# CircuitTestZak1.net
KiCad netlist of a schematic drawn in Altium Designer
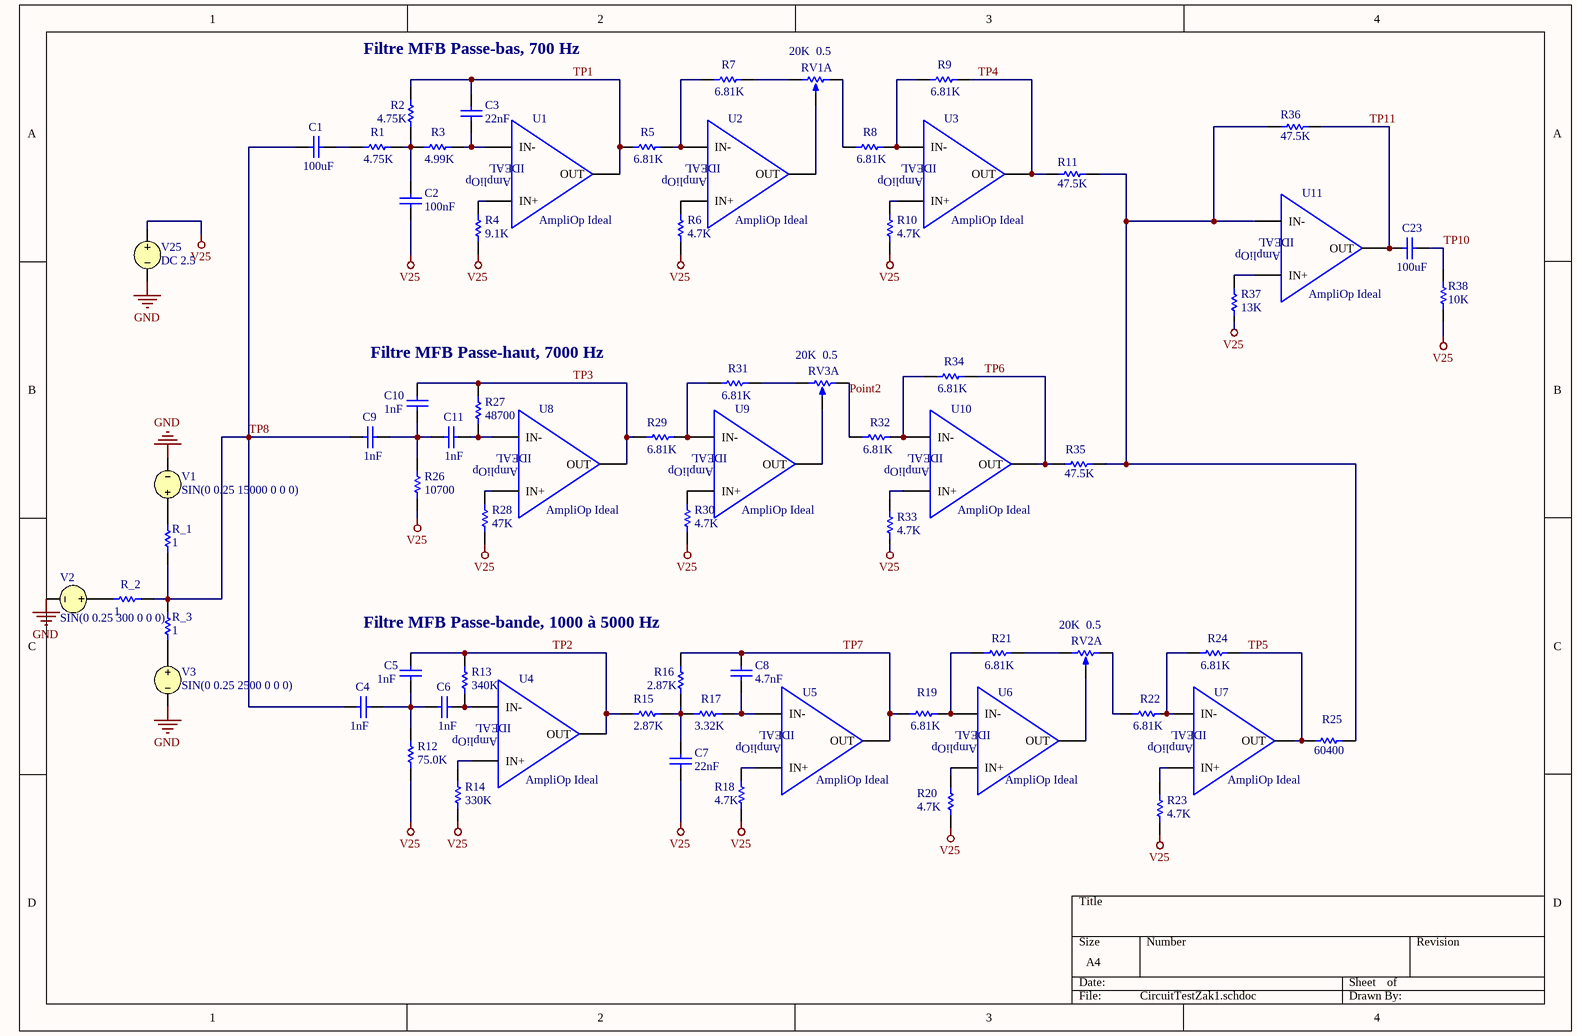
[diagram p0: CircuitTestZak1.schdoc]

(export (version "E")
  (design (tool "Eeschema 10.0.6"))
  (components
    (comp (ref "C1")
      (value "100uF")
      (footprint "RAD-0.3")
      (description "Capacitor")
      (fields (field (name "Comment") "Cap") (field (name "PUBLISHER") "Altium Limited"))
      (libsource (lib "Miscellaneous Devices") (part "Cap"))
    )
    (comp (ref "C2")
      (value "100nF")
      (footprint "RAD-0.3")
      (description "Capacitor")
      (fields (field (name "Comment") "Cap") (field (name "PUBLISHER") "Altium Limited"))
      (libsource (lib "Miscellaneous Devices") (part "Cap"))
    )
    (comp (ref "C3")
      (value "22nF")
      (footprint "RAD-0.3")
      (description "Capacitor")
      (fields (field (name "Comment") "Cap") (field (name "PUBLISHER") "Altium Limited"))
      (libsource (lib "Miscellaneous Devices") (part "Cap"))
    )
    (comp (ref "C4")
      (value "1nF")
      (footprint "RAD-0.3")
      (description "Capacitor")
      (fields (field (name "Comment") "Cap") (field (name "PUBLISHER") "Altium Limited"))
      (libsource (lib "Miscellaneous Devices") (part "Cap"))
    )
    (comp (ref "C5")
      (value "1nF")
      (footprint "RAD-0.3")
      (description "Capacitor")
      (fields (field (name "Comment") "Cap") (field (name "PUBLISHER") "Altium Limited"))
      (libsource (lib "Miscellaneous Devices") (part "Cap"))
    )
    (comp (ref "C6")
      (value "1nF")
      (footprint "RAD-0.3")
      (description "Capacitor")
      (fields (field (name "Comment") "Cap") (field (name "PUBLISHER") "Altium Limited"))
      (libsource (lib "Miscellaneous Devices") (part "Cap"))
    )
    (comp (ref "C7")
      (value "22nF")
      (footprint "RAD-0.3")
      (description "Capacitor")
      (fields (field (name "Comment") "Cap") (field (name "PUBLISHER") "Altium Limited"))
      (libsource (lib "Miscellaneous Devices") (part "Cap"))
    )
    (comp (ref "C8")
      (value "4.7nF")
      (footprint "RAD-0.3")
      (description "Capacitor")
      (fields (field (name "Comment") "Cap") (field (name "PUBLISHER") "Altium Limited"))
      (libsource (lib "Miscellaneous Devices") (part "Cap"))
    )
    (comp (ref "C9")
      (value "1nF")
      (footprint "RAD-0.3")
      (description "Capacitor")
      (fields (field (name "Comment") "Cap") (field (name "PUBLISHER") "Altium Limited"))
      (libsource (lib "Miscellaneous Devices") (part "Cap"))
    )
    (comp (ref "C10")
      (value "1nF")
      (footprint "RAD-0.3")
      (description "Capacitor")
      (fields (field (name "Comment") "Cap") (field (name "PUBLISHER") "Altium Limited"))
      (libsource (lib "Miscellaneous Devices") (part "Cap"))
    )
    (comp (ref "C11")
      (value "1nF")
      (footprint "RAD-0.3")
      (description "Capacitor")
      (fields (field (name "Comment") "Cap") (field (name "PUBLISHER") "Altium Limited"))
      (libsource (lib "Miscellaneous Devices") (part "Cap"))
    )
    (comp (ref "C23")
      (value "100uF")
      (footprint "RAD-0.3")
      (description "Capacitor")
      (fields (field (name "Comment") "Cap") (field (name "PUBLISHER") "Altium Limited"))
      (libsource (lib "Miscellaneous Devices") (part "Cap"))
    )
    (comp (ref "R1")
      (value "4.75K")
      (footprint "AXIAL-0.3")
      (description "Resistor")
      (fields (field (name "Comment") "Res1") (field (name "PUBLISHER") "Altium Limited"))
      (libsource (lib "Miscellaneous Devices") (part "Res1"))
    )
    (comp (ref "R2")
      (value "4.75K")
      (footprint "AXIAL-0.3")
      (description "Resistor")
      (fields (field (name "Comment") "Res1") (field (name "PUBLISHER") "Altium Limited"))
      (libsource (lib "Miscellaneous Devices") (part "Res1"))
    )
    (comp (ref "R3")
      (value "4.99K")
      (footprint "AXIAL-0.3")
      (description "Resistor")
      (fields (field (name "Comment") "Res1") (field (name "PUBLISHER") "Altium Limited"))
      (libsource (lib "Miscellaneous Devices") (part "Res1"))
    )
    (comp (ref "R4")
      (value "9.1K")
      (footprint "AXIAL-0.3")
      (description "Resistor")
      (fields (field (name "Comment") "Res1") (field (name "PUBLISHER") "Altium Limited"))
      (libsource (lib "Miscellaneous Devices") (part "Res1"))
    )
    (comp (ref "R5")
      (value "6.81K")
      (footprint "AXIAL-0.3")
      (description "Resistor")
      (fields (field (name "Comment") "Res1") (field (name "PUBLISHER") "Altium Limited"))
      (libsource (lib "Miscellaneous Devices") (part "Res1"))
    )
    (comp (ref "R6")
      (value "4.7K")
      (footprint "AXIAL-0.3")
      (description "Resistor")
      (fields (field (name "Comment") "Res1") (field (name "PUBLISHER") "Altium Limited"))
      (libsource (lib "Miscellaneous Devices") (part "Res1"))
    )
    (comp (ref "R7")
      (value "6.81K")
      (footprint "AXIAL-0.3")
      (description "Resistor")
      (fields (field (name "Comment") "Res1") (field (name "PUBLISHER") "Altium Limited"))
      (libsource (lib "Miscellaneous Devices") (part "Res1"))
    )
    (comp (ref "R8")
      (value "6.81K")
      (footprint "AXIAL-0.3")
      (description "Resistor")
      (fields (field (name "Comment") "Res1") (field (name "PUBLISHER") "Altium Limited"))
      (libsource (lib "Miscellaneous Devices") (part "Res1"))
    )
    (comp (ref "R9")
      (value "6.81K")
      (footprint "AXIAL-0.3")
      (description "Resistor")
      (fields (field (name "Comment") "Res1") (field (name "PUBLISHER") "Altium Limited"))
      (libsource (lib "Miscellaneous Devices") (part "Res1"))
    )
    (comp (ref "R10")
      (value "4.7K")
      (footprint "AXIAL-0.3")
      (description "Resistor")
      (fields (field (name "Comment") "Res1") (field (name "PUBLISHER") "Altium Limited"))
      (libsource (lib "Miscellaneous Devices") (part "Res1"))
    )
    (comp (ref "R11")
      (value "47.5K")
      (footprint "AXIAL-0.3")
      (description "Resistor")
      (fields (field (name "Comment") "Res1") (field (name "PUBLISHER") "Altium Limited"))
      (libsource (lib "Miscellaneous Devices") (part "Res1"))
    )
    (comp (ref "R12")
      (value "75.0K")
      (footprint "AXIAL-0.3")
      (description "Resistor")
      (fields (field (name "Comment") "Res1") (field (name "PUBLISHER") "Altium Limited"))
      (libsource (lib "Miscellaneous Devices") (part "Res1"))
    )
    (comp (ref "R13")
      (value "340K")
      (footprint "AXIAL-0.3")
      (description "Resistor")
      (fields (field (name "Comment") "Res1") (field (name "PUBLISHER") "Altium Limited"))
      (libsource (lib "Miscellaneous Devices") (part "Res1"))
    )
    (comp (ref "R14")
      (value "330K")
      (footprint "AXIAL-0.3")
      (description "Resistor")
      (fields (field (name "Comment") "Res1") (field (name "PUBLISHER") "Altium Limited"))
      (libsource (lib "Miscellaneous Devices") (part "Res1"))
    )
    (comp (ref "R15")
      (value "2.87K")
      (footprint "AXIAL-0.3")
      (description "Resistor")
      (fields (field (name "Comment") "Res1") (field (name "PUBLISHER") "Altium Limited"))
      (libsource (lib "Miscellaneous Devices") (part "Res1"))
    )
    (comp (ref "R16")
      (value "2.87K")
      (footprint "AXIAL-0.3")
      (description "Resistor")
      (fields (field (name "Comment") "Res1") (field (name "PUBLISHER") "Altium Limited"))
      (libsource (lib "Miscellaneous Devices") (part "Res1"))
    )
    (comp (ref "R17")
      (value "3.32K")
      (footprint "AXIAL-0.3")
      (description "Resistor")
      (fields (field (name "Comment") "Res1") (field (name "PUBLISHER") "Altium Limited"))
      (libsource (lib "Miscellaneous Devices") (part "Res1"))
    )
    (comp (ref "R18")
      (value "4.7K")
      (footprint "AXIAL-0.3")
      (description "Resistor")
      (fields (field (name "Comment") "Res1") (field (name "PUBLISHER") "Altium Limited"))
      (libsource (lib "Miscellaneous Devices") (part "Res1"))
    )
    (comp (ref "R19")
      (value "6.81K")
      (footprint "AXIAL-0.3")
      (description "Resistor")
      (fields (field (name "Comment") "Res1") (field (name "PUBLISHER") "Altium Limited"))
      (libsource (lib "Miscellaneous Devices") (part "Res1"))
    )
    (comp (ref "R20")
      (value "4.7K")
      (footprint "AXIAL-0.3")
      (description "Resistor")
      (fields (field (name "Comment") "Res1") (field (name "PUBLISHER") "Altium Limited"))
      (libsource (lib "Miscellaneous Devices") (part "Res1"))
    )
    (comp (ref "R21")
      (value "6.81K")
      (footprint "AXIAL-0.3")
      (description "Resistor")
      (fields (field (name "Comment") "Res1") (field (name "PUBLISHER") "Altium Limited"))
      (libsource (lib "Miscellaneous Devices") (part "Res1"))
    )
    (comp (ref "R22")
      (value "6.81K")
      (footprint "AXIAL-0.3")
      (description "Resistor")
      (fields (field (name "Comment") "Res1") (field (name "PUBLISHER") "Altium Limited"))
      (libsource (lib "Miscellaneous Devices") (part "Res1"))
    )
    (comp (ref "R23")
      (value "4.7K")
      (footprint "AXIAL-0.3")
      (description "Resistor")
      (fields (field (name "Comment") "Res1") (field (name "PUBLISHER") "Altium Limited"))
      (libsource (lib "Miscellaneous Devices") (part "Res1"))
    )
    (comp (ref "R24")
      (value "6.81K")
      (footprint "AXIAL-0.3")
      (description "Resistor")
      (fields (field (name "Comment") "Res1") (field (name "PUBLISHER") "Altium Limited"))
      (libsource (lib "Miscellaneous Devices") (part "Res1"))
    )
    (comp (ref "R25")
      (value "60400")
      (footprint "AXIAL-0.3")
      (description "Resistor")
      (fields (field (name "Comment") "Res1") (field (name "PUBLISHER") "Altium Limited"))
      (libsource (lib "Miscellaneous Devices") (part "Res1"))
    )
    (comp (ref "R26")
      (value "10700")
      (footprint "AXIAL-0.3")
      (description "Resistor")
      (fields (field (name "Comment") "Res1") (field (name "PUBLISHER") "Altium Limited"))
      (libsource (lib "Miscellaneous Devices") (part "Res1"))
    )
    (comp (ref "R27")
      (value "48700")
      (footprint "AXIAL-0.3")
      (description "Resistor")
      (fields (field (name "Comment") "Res1") (field (name "PUBLISHER") "Altium Limited"))
      (libsource (lib "Miscellaneous Devices") (part "Res1"))
    )
    (comp (ref "R28")
      (value "47K")
      (footprint "AXIAL-0.3")
      (description "Resistor")
      (fields (field (name "Comment") "Res1") (field (name "PUBLISHER") "Altium Limited"))
      (libsource (lib "Miscellaneous Devices") (part "Res1"))
    )
    (comp (ref "R29")
      (value "6.81K")
      (footprint "AXIAL-0.3")
      (description "Resistor")
      (fields (field (name "Comment") "Res1") (field (name "PUBLISHER") "Altium Limited"))
      (libsource (lib "Miscellaneous Devices") (part "Res1"))
    )
    (comp (ref "R30")
      (value "4.7K")
      (footprint "AXIAL-0.3")
      (description "Resistor")
      (fields (field (name "Comment") "Res1") (field (name "PUBLISHER") "Altium Limited"))
      (libsource (lib "Miscellaneous Devices") (part "Res1"))
    )
    (comp (ref "R31")
      (value "6.81K")
      (footprint "AXIAL-0.3")
      (description "Resistor")
      (fields (field (name "Comment") "Res1") (field (name "PUBLISHER") "Altium Limited"))
      (libsource (lib "Miscellaneous Devices") (part "Res1"))
    )
    (comp (ref "R32")
      (value "6.81K")
      (footprint "AXIAL-0.3")
      (description "Resistor")
      (fields (field (name "Comment") "Res1") (field (name "PUBLISHER") "Altium Limited"))
      (libsource (lib "Miscellaneous Devices") (part "Res1"))
    )
    (comp (ref "R33")
      (value "4.7K")
      (footprint "AXIAL-0.3")
      (description "Resistor")
      (fields (field (name "Comment") "Res1") (field (name "PUBLISHER") "Altium Limited"))
      (libsource (lib "Miscellaneous Devices") (part "Res1"))
    )
    (comp (ref "R34")
      (value "6.81K")
      (footprint "AXIAL-0.3")
      (description "Resistor")
      (fields (field (name "Comment") "Res1") (field (name "PUBLISHER") "Altium Limited"))
      (libsource (lib "Miscellaneous Devices") (part "Res1"))
    )
    (comp (ref "R35")
      (value "47.5K")
      (footprint "AXIAL-0.3")
      (description "Resistor")
      (fields (field (name "Comment") "Res1") (field (name "PUBLISHER") "Altium Limited"))
      (libsource (lib "Miscellaneous Devices") (part "Res1"))
    )
    (comp (ref "R36")
      (value "47.5K")
      (footprint "AXIAL-0.3")
      (description "Resistor")
      (fields (field (name "Comment") "Res1") (field (name "PUBLISHER") "Altium Limited"))
      (libsource (lib "Miscellaneous Devices") (part "Res1"))
    )
    (comp (ref "R37")
      (value "13K")
      (footprint "AXIAL-0.3")
      (description "Resistor")
      (fields (field (name "Comment") "Res1") (field (name "PUBLISHER") "Altium Limited"))
      (libsource (lib "Miscellaneous Devices") (part "Res1"))
    )
    (comp (ref "R38")
      (value "10K")
      (footprint "AXIAL-0.3")
      (description "Resistor")
      (fields (field (name "Comment") "Res1") (field (name "PUBLISHER") "Altium Limited"))
      (libsource (lib "Miscellaneous Devices") (part "Res1"))
    )
    (comp (ref "RV1A")
      (value "20K")
      (footprint "VR5")
      (description "Potentiometer")
      (fields
        (field (name "SET POSITION") "0.5")
        (field (name "Comment") "RPot")
        (field (name "PUBLISHER") "Altium Limited")
      )
      (libsource (lib "Miscellaneous Devices") (part "RPot"))
    )
    (comp (ref "RV2A")
      (value "20K")
      (footprint "VR5")
      (description "Potentiometer")
      (fields
        (field (name "SET POSITION") "0.5")
        (field (name "Comment") "RPot")
        (field (name "PUBLISHER") "Altium Limited")
      )
      (libsource (lib "Miscellaneous Devices") (part "RPot"))
    )
    (comp (ref "RV3A")
      (value "20K")
      (footprint "VR5")
      (description "Potentiometer")
      (fields
        (field (name "SET POSITION") "0.5")
        (field (name "Comment") "RPot")
        (field (name "PUBLISHER") "Altium Limited")
      )
      (libsource (lib "Miscellaneous Devices") (part "RPot"))
    )
    (comp (ref "R_1")
      (value "1")
      (footprint "AXIAL-0.3")
      (description "Resistor")
      (fields (field (name "Comment") "Res1") (field (name "PUBLISHER") "Altium Limited"))
      (libsource (lib "Miscellaneous Devices") (part "Res1"))
    )
    (comp (ref "R_2")
      (value "1")
      (footprint "AXIAL-0.3")
      (description "Resistor")
      (fields (field (name "Comment") "Res1") (field (name "PUBLISHER") "Altium Limited"))
      (libsource (lib "Miscellaneous Devices") (part "Res1"))
    )
    (comp (ref "R_3")
      (value "1")
      (footprint "AXIAL-0.3")
      (description "Resistor")
      (fields (field (name "Comment") "Res1") (field (name "PUBLISHER") "Altium Limited"))
      (libsource (lib "Miscellaneous Devices") (part "Res1"))
    )
    (comp (ref "U1") (value "AmpliOp Ideal") (libsource (lib "Librarie_S2") (part "AmpliOp_ideal")))
    (comp (ref "U2") (value "AmpliOp Ideal") (libsource (lib "Librarie_S2") (part "AmpliOp_ideal")))
    (comp (ref "U3") (value "AmpliOp Ideal") (libsource (lib "Librarie_S2") (part "AmpliOp_ideal")))
    (comp (ref "U4") (value "AmpliOp Ideal") (libsource (lib "Librarie_S2") (part "AmpliOp_ideal")))
    (comp (ref "U5") (value "AmpliOp Ideal") (libsource (lib "Librarie_S2") (part "AmpliOp_ideal")))
    (comp (ref "U6") (value "AmpliOp Ideal") (libsource (lib "Librarie_S2") (part "AmpliOp_ideal")))
    (comp (ref "U7") (value "AmpliOp Ideal") (libsource (lib "Librarie_S2") (part "AmpliOp_ideal")))
    (comp (ref "U8") (value "AmpliOp Ideal") (libsource (lib "Librarie_S2") (part "AmpliOp_ideal")))
    (comp (ref "U9") (value "AmpliOp Ideal") (libsource (lib "Librarie_S2") (part "AmpliOp_ideal")))
    (comp (ref "U10") (value "AmpliOp Ideal") (libsource (lib "Librarie_S2") (part "AmpliOp_ideal")))
    (comp (ref "U11") (value "AmpliOp Ideal") (libsource (lib "Librarie_S2") (part "AmpliOp_ideal")))
    (comp (ref "V1")
      (value "SIN(0 0.25 15000 0 0 0)")
      (description "Voltage Source")
      (fields (field (name "PUBLISHER") "Altium Limited"))
      (libsource (lib "Simulation Generic Components") (part "VSRC"))
    )
    (comp (ref "V2")
      (value "SIN(0 0.25 300 0 0 0)")
      (description "Voltage Source")
      (fields (field (name "PUBLISHER") "Altium Limited"))
      (libsource (lib "Simulation Generic Components") (part "VSRC"))
    )
    (comp (ref "V3")
      (value "SIN(0 0.25 2500 0 0 0)")
      (description "Voltage Source")
      (fields (field (name "PUBLISHER") "Altium Limited"))
      (libsource (lib "Simulation Generic Components") (part "VSRC"))
    )
    (comp (ref "V25")
      (value "DC 2.5")
      (description "Voltage Source")
      (fields (field (name "PUBLISHER") "Altium Limited"))
      (libsource (lib "Simulation Generic Components") (part "VSRC"))
    )
  )
  (nets
    (net (code "1") (name "/Point2") (class "Default")
      (node (ref "R32") (pin "1") (pinfunction "1_1") (pintype "passive"))
      (node (ref "RV3A") (pin "2") (pinfunction "BOT_2") (pintype "passive"))
    )
    (net (code "2") (name "/TP1") (class "Default")
      (node (ref "C3") (pin "1") (pinfunction "1_1") (pintype "passive"))
      (node (ref "R2") (pin "1") (pinfunction "1_1") (pintype "passive"))
      (node (ref "R5") (pin "1") (pinfunction "1_1") (pintype "passive"))
      (node (ref "U1") (pin "3") (pinfunction "OUT_3") (pintype "passive"))
    )
    (net (code "3") (name "/TP2") (class "Default")
      (node (ref "C5") (pin "1") (pinfunction "1_1") (pintype "passive"))
      (node (ref "R13") (pin "1") (pinfunction "1_1") (pintype "passive"))
      (node (ref "R15") (pin "1") (pinfunction "1_1") (pintype "passive"))
      (node (ref "U4") (pin "3") (pinfunction "OUT_3") (pintype "passive"))
    )
    (net (code "4") (name "/TP3") (class "Default")
      (node (ref "C10") (pin "1") (pinfunction "1_1") (pintype "passive"))
      (node (ref "R27") (pin "1") (pinfunction "1_1") (pintype "passive"))
      (node (ref "R29") (pin "1") (pinfunction "1_1") (pintype "passive"))
      (node (ref "U8") (pin "3") (pinfunction "OUT_3") (pintype "passive"))
    )
    (net (code "5") (name "/TP4") (class "Default")
      (node (ref "R11") (pin "1") (pinfunction "1_1") (pintype "passive"))
      (node (ref "R9") (pin "2") (pinfunction "2_2") (pintype "passive"))
      (node (ref "U3") (pin "3") (pinfunction "OUT_3") (pintype "passive"))
    )
    (net (code "6") (name "/TP5") (class "Default")
      (node (ref "R24") (pin "2") (pinfunction "2_2") (pintype "passive"))
      (node (ref "R25") (pin "1") (pinfunction "1_1") (pintype "passive"))
      (node (ref "U7") (pin "3") (pinfunction "OUT_3") (pintype "passive"))
    )
    (net (code "7") (name "/TP6") (class "Default")
      (node (ref "R34") (pin "2") (pinfunction "2_2") (pintype "passive"))
      (node (ref "R35") (pin "1") (pinfunction "1_1") (pintype "passive"))
      (node (ref "U10") (pin "3") (pinfunction "OUT_3") (pintype "passive"))
    )
    (net (code "8") (name "/TP7") (class "Default")
      (node (ref "C8") (pin "1") (pinfunction "1_1") (pintype "passive"))
      (node (ref "R16") (pin "1") (pinfunction "1_1") (pintype "passive"))
      (node (ref "R19") (pin "1") (pinfunction "1_1") (pintype "passive"))
      (node (ref "U5") (pin "3") (pinfunction "OUT_3") (pintype "passive"))
    )
    (net (code "9") (name "/TP8") (class "Default")
      (node (ref "C1") (pin "1") (pinfunction "1_1") (pintype "passive"))
      (node (ref "C4") (pin "1") (pinfunction "1_1") (pintype "passive"))
      (node (ref "C9") (pin "1") (pinfunction "1_1") (pintype "passive"))
      (node (ref "R_1") (pin "1") (pinfunction "1_1") (pintype "passive"))
      (node (ref "R_2") (pin "2") (pinfunction "2_2") (pintype "passive"))
      (node (ref "R_3") (pin "2") (pinfunction "2_2") (pintype "passive"))
    )
    (net (code "10") (name "/TP10") (class "Default")
      (node (ref "C23") (pin "2") (pinfunction "2_2") (pintype "passive"))
      (node (ref "R38") (pin "2") (pinfunction "2_2") (pintype "passive"))
    )
    (net (code "11") (name "/TP11") (class "Default")
      (node (ref "C23") (pin "1") (pinfunction "1_1") (pintype "passive"))
      (node (ref "R36") (pin "2") (pinfunction "2_2") (pintype "passive"))
      (node (ref "U11") (pin "3") (pinfunction "OUT_3") (pintype "passive"))
    )
    (net (code "12") (name "GND") (class "Default")
      (node (ref "V1") (pin "2") (pinfunction "2_2") (pintype "passive"))
      (node (ref "V2") (pin "2") (pinfunction "2_2") (pintype "passive"))
      (node (ref "V25") (pin "2") (pinfunction "2_2") (pintype "passive"))
      (node (ref "V3") (pin "2") (pinfunction "2_2") (pintype "passive"))
    )
    (net (code "13") (name "Net-(C1-Pad2)") (class "Default")
      (node (ref "C1") (pin "2") (pinfunction "2_2") (pintype "passive"))
      (node (ref "R1") (pin "1") (pinfunction "1_1") (pintype "passive"))
    )
    (net (code "14") (name "Net-(C2-Pad1)") (class "Default")
      (node (ref "C2") (pin "1") (pinfunction "1_1") (pintype "passive"))
      (node (ref "R1") (pin "2") (pinfunction "2_2") (pintype "passive"))
      (node (ref "R2") (pin "2") (pinfunction "2_2") (pintype "passive"))
      (node (ref "R3") (pin "1") (pinfunction "1_1") (pintype "passive"))
    )
    (net (code "15") (name "Net-(C4-Pad2)") (class "Default")
      (node (ref "C4") (pin "2") (pinfunction "2_2") (pintype "passive"))
      (node (ref "C5") (pin "2") (pinfunction "2_2") (pintype "passive"))
      (node (ref "C6") (pin "1") (pinfunction "1_1") (pintype "passive"))
      (node (ref "R12") (pin "1") (pinfunction "1_1") (pintype "passive"))
    )
    (net (code "16") (name "Net-(C7-Pad1)") (class "Default")
      (node (ref "C7") (pin "1") (pinfunction "1_1") (pintype "passive"))
      (node (ref "R15") (pin "2") (pinfunction "2_2") (pintype "passive"))
      (node (ref "R16") (pin "2") (pinfunction "2_2") (pintype "passive"))
      (node (ref "R17") (pin "1") (pinfunction "1_1") (pintype "passive"))
    )
    (net (code "17") (name "Net-(C10-Pad2)") (class "Default")
      (node (ref "C10") (pin "2") (pinfunction "2_2") (pintype "passive"))
      (node (ref "C11") (pin "1") (pinfunction "1_1") (pintype "passive"))
      (node (ref "C9") (pin "2") (pinfunction "2_2") (pintype "passive"))
      (node (ref "R26") (pin "1") (pinfunction "1_1") (pintype "passive"))
    )
    (net (code "18") (name "Net-(RV1A-BOT)") (class "Default")
      (node (ref "R8") (pin "1") (pinfunction "1_1") (pintype "passive"))
      (node (ref "RV1A") (pin "2") (pinfunction "BOT_2") (pintype "passive"))
    )
    (net (code "19") (name "Net-(RV1A-TAP)") (class "Default")
      (node (ref "RV1A") (pin "3") (pinfunction "TAP_3") (pintype "passive"))
      (node (ref "U2") (pin "3") (pinfunction "OUT_3") (pintype "passive"))
    )
    (net (code "20") (name "Net-(RV1A-TOP)") (class "Default")
      (node (ref "R7") (pin "2") (pinfunction "2_2") (pintype "passive"))
      (node (ref "RV1A") (pin "1") (pinfunction "TOP_1") (pintype "passive"))
    )
    (net (code "21") (name "Net-(RV2A-BOT)") (class "Default")
      (node (ref "R22") (pin "1") (pinfunction "1_1") (pintype "passive"))
      (node (ref "RV2A") (pin "2") (pinfunction "BOT_2") (pintype "passive"))
    )
    (net (code "22") (name "Net-(RV2A-TAP)") (class "Default")
      (node (ref "RV2A") (pin "3") (pinfunction "TAP_3") (pintype "passive"))
      (node (ref "U6") (pin "3") (pinfunction "OUT_3") (pintype "passive"))
    )
    (net (code "23") (name "Net-(RV2A-TOP)") (class "Default")
      (node (ref "R21") (pin "2") (pinfunction "2_2") (pintype "passive"))
      (node (ref "RV2A") (pin "1") (pinfunction "TOP_1") (pintype "passive"))
    )
    (net (code "24") (name "Net-(RV3A-TAP)") (class "Default")
      (node (ref "RV3A") (pin "3") (pinfunction "TAP_3") (pintype "passive"))
      (node (ref "U9") (pin "3") (pinfunction "OUT_3") (pintype "passive"))
    )
    (net (code "25") (name "Net-(RV3A-TOP)") (class "Default")
      (node (ref "R31") (pin "2") (pinfunction "2_2") (pintype "passive"))
      (node (ref "RV3A") (pin "1") (pinfunction "TOP_1") (pintype "passive"))
    )
    (net (code "26") (name "Net-(R_1-Pad2)") (class "Default")
      (node (ref "R_1") (pin "2") (pinfunction "2_2") (pintype "passive"))
      (node (ref "V1") (pin "1") (pinfunction "1_1") (pintype "passive"))
    )
    (net (code "27") (name "Net-(R_2-Pad1)") (class "Default")
      (node (ref "R_2") (pin "1") (pinfunction "1_1") (pintype "passive"))
      (node (ref "V2") (pin "1") (pinfunction "1_1") (pintype "passive"))
    )
    (net (code "28") (name "Net-(R_3-Pad1)") (class "Default")
      (node (ref "R_3") (pin "1") (pinfunction "1_1") (pintype "passive"))
      (node (ref "V3") (pin "1") (pinfunction "1_1") (pintype "passive"))
    )
    (net (code "29") (name "Net-(U1-IN+)") (class "Default")
      (node (ref "R4") (pin "1") (pinfunction "1_1") (pintype "passive"))
      (node (ref "U1") (pin "1") (pinfunction "IN+_1") (pintype "passive"))
    )
    (net (code "30") (name "Net-(U1-IN-)") (class "Default")
      (node (ref "C3") (pin "2") (pinfunction "2_2") (pintype "passive"))
      (node (ref "R3") (pin "2") (pinfunction "2_2") (pintype "passive"))
      (node (ref "U1") (pin "2") (pinfunction "IN-_2") (pintype "passive"))
    )
    (net (code "31") (name "Net-(U2-IN+)") (class "Default")
      (node (ref "R6") (pin "1") (pinfunction "1_1") (pintype "passive"))
      (node (ref "U2") (pin "1") (pinfunction "IN+_1") (pintype "passive"))
    )
    (net (code "32") (name "Net-(U2-IN-)") (class "Default")
      (node (ref "R5") (pin "2") (pinfunction "2_2") (pintype "passive"))
      (node (ref "R7") (pin "1") (pinfunction "1_1") (pintype "passive"))
      (node (ref "U2") (pin "2") (pinfunction "IN-_2") (pintype "passive"))
    )
    (net (code "33") (name "Net-(U3-IN+)") (class "Default")
      (node (ref "R10") (pin "1") (pinfunction "1_1") (pintype "passive"))
      (node (ref "U3") (pin "1") (pinfunction "IN+_1") (pintype "passive"))
    )
    (net (code "34") (name "Net-(U3-IN-)") (class "Default")
      (node (ref "R8") (pin "2") (pinfunction "2_2") (pintype "passive"))
      (node (ref "R9") (pin "1") (pinfunction "1_1") (pintype "passive"))
      (node (ref "U3") (pin "2") (pinfunction "IN-_2") (pintype "passive"))
    )
    (net (code "35") (name "Net-(U4-IN+)") (class "Default")
      (node (ref "R14") (pin "1") (pinfunction "1_1") (pintype "passive"))
      (node (ref "U4") (pin "1") (pinfunction "IN+_1") (pintype "passive"))
    )
    (net (code "36") (name "Net-(U4-IN-)") (class "Default")
      (node (ref "C6") (pin "2") (pinfunction "2_2") (pintype "passive"))
      (node (ref "R13") (pin "2") (pinfunction "2_2") (pintype "passive"))
      (node (ref "U4") (pin "2") (pinfunction "IN-_2") (pintype "passive"))
    )
    (net (code "37") (name "Net-(U5-IN+)") (class "Default")
      (node (ref "R18") (pin "1") (pinfunction "1_1") (pintype "passive"))
      (node (ref "U5") (pin "1") (pinfunction "IN+_1") (pintype "passive"))
    )
    (net (code "38") (name "Net-(U5-IN-)") (class "Default")
      (node (ref "C8") (pin "2") (pinfunction "2_2") (pintype "passive"))
      (node (ref "R17") (pin "2") (pinfunction "2_2") (pintype "passive"))
      (node (ref "U5") (pin "2") (pinfunction "IN-_2") (pintype "passive"))
    )
    (net (code "39") (name "Net-(U6-IN+)") (class "Default")
      (node (ref "R20") (pin "1") (pinfunction "1_1") (pintype "passive"))
      (node (ref "U6") (pin "1") (pinfunction "IN+_1") (pintype "passive"))
    )
    (net (code "40") (name "Net-(U6-IN-)") (class "Default")
      (node (ref "R19") (pin "2") (pinfunction "2_2") (pintype "passive"))
      (node (ref "R21") (pin "1") (pinfunction "1_1") (pintype "passive"))
      (node (ref "U6") (pin "2") (pinfunction "IN-_2") (pintype "passive"))
    )
    (net (code "41") (name "Net-(U7-IN+)") (class "Default")
      (node (ref "R23") (pin "1") (pinfunction "1_1") (pintype "passive"))
      (node (ref "U7") (pin "1") (pinfunction "IN+_1") (pintype "passive"))
    )
    (net (code "42") (name "Net-(U7-IN-)") (class "Default")
      (node (ref "R22") (pin "2") (pinfunction "2_2") (pintype "passive"))
      (node (ref "R24") (pin "1") (pinfunction "1_1") (pintype "passive"))
      (node (ref "U7") (pin "2") (pinfunction "IN-_2") (pintype "passive"))
    )
    (net (code "43") (name "Net-(U8-IN+)") (class "Default")
      (node (ref "R28") (pin "1") (pinfunction "1_1") (pintype "passive"))
      (node (ref "U8") (pin "1") (pinfunction "IN+_1") (pintype "passive"))
    )
    (net (code "44") (name "Net-(U8-IN-)") (class "Default")
      (node (ref "C11") (pin "2") (pinfunction "2_2") (pintype "passive"))
      (node (ref "R27") (pin "2") (pinfunction "2_2") (pintype "passive"))
      (node (ref "U8") (pin "2") (pinfunction "IN-_2") (pintype "passive"))
    )
    (net (code "45") (name "Net-(U9-IN+)") (class "Default")
      (node (ref "R30") (pin "1") (pinfunction "1_1") (pintype "passive"))
      (node (ref "U9") (pin "1") (pinfunction "IN+_1") (pintype "passive"))
    )
    (net (code "46") (name "Net-(U9-IN-)") (class "Default")
      (node (ref "R29") (pin "2") (pinfunction "2_2") (pintype "passive"))
      (node (ref "R31") (pin "1") (pinfunction "1_1") (pintype "passive"))
      (node (ref "U9") (pin "2") (pinfunction "IN-_2") (pintype "passive"))
    )
    (net (code "47") (name "Net-(U10-IN+)") (class "Default")
      (node (ref "R33") (pin "1") (pinfunction "1_1") (pintype "passive"))
      (node (ref "U10") (pin "1") (pinfunction "IN+_1") (pintype "passive"))
    )
    (net (code "48") (name "Net-(U10-IN-)") (class "Default")
      (node (ref "R32") (pin "2") (pinfunction "2_2") (pintype "passive"))
      (node (ref "R34") (pin "1") (pinfunction "1_1") (pintype "passive"))
      (node (ref "U10") (pin "2") (pinfunction "IN-_2") (pintype "passive"))
    )
    (net (code "49") (name "Net-(U11-IN+)") (class "Default")
      (node (ref "R37") (pin "1") (pinfunction "1_1") (pintype "passive"))
      (node (ref "U11") (pin "1") (pinfunction "IN+_1") (pintype "passive"))
    )
    (net (code "50") (name "Net-(U11-IN-)") (class "Default")
      (node (ref "R11") (pin "2") (pinfunction "2_2") (pintype "passive"))
      (node (ref "R25") (pin "2") (pinfunction "2_2") (pintype "passive"))
      (node (ref "R35") (pin "2") (pinfunction "2_2") (pintype "passive"))
      (node (ref "R36") (pin "1") (pinfunction "1_1") (pintype "passive"))
      (node (ref "U11") (pin "2") (pinfunction "IN-_2") (pintype "passive"))
    )
    (net (code "51") (name "V25") (class "Default")
      (node (ref "C2") (pin "2") (pinfunction "2_2") (pintype "passive"))
      (node (ref "C7") (pin "2") (pinfunction "2_2") (pintype "passive"))
      (node (ref "R10") (pin "2") (pinfunction "2_2") (pintype "passive"))
      (node (ref "R12") (pin "2") (pinfunction "2_2") (pintype "passive"))
      (node (ref "R14") (pin "2") (pinfunction "2_2") (pintype "passive"))
      (node (ref "R18") (pin "2") (pinfunction "2_2") (pintype "passive"))
      (node (ref "R20") (pin "2") (pinfunction "2_2") (pintype "passive"))
      (node (ref "R23") (pin "2") (pinfunction "2_2") (pintype "passive"))
      (node (ref "R26") (pin "2") (pinfunction "2_2") (pintype "passive"))
      (node (ref "R28") (pin "2") (pinfunction "2_2") (pintype "passive"))
      (node (ref "R30") (pin "2") (pinfunction "2_2") (pintype "passive"))
      (node (ref "R33") (pin "2") (pinfunction "2_2") (pintype "passive"))
      (node (ref "R37") (pin "2") (pinfunction "2_2") (pintype "passive"))
      (node (ref "R38") (pin "1") (pinfunction "1_1") (pintype "passive"))
      (node (ref "R4") (pin "2") (pinfunction "2_2") (pintype "passive"))
      (node (ref "R6") (pin "2") (pinfunction "2_2") (pintype "passive"))
      (node (ref "V25") (pin "1") (pinfunction "1_1") (pintype "passive"))
    )
  )
)
